# SH2_-_17V_BUCK_CONVERTER.net
KiCad netlist of a schematic drawn in Altium Designer
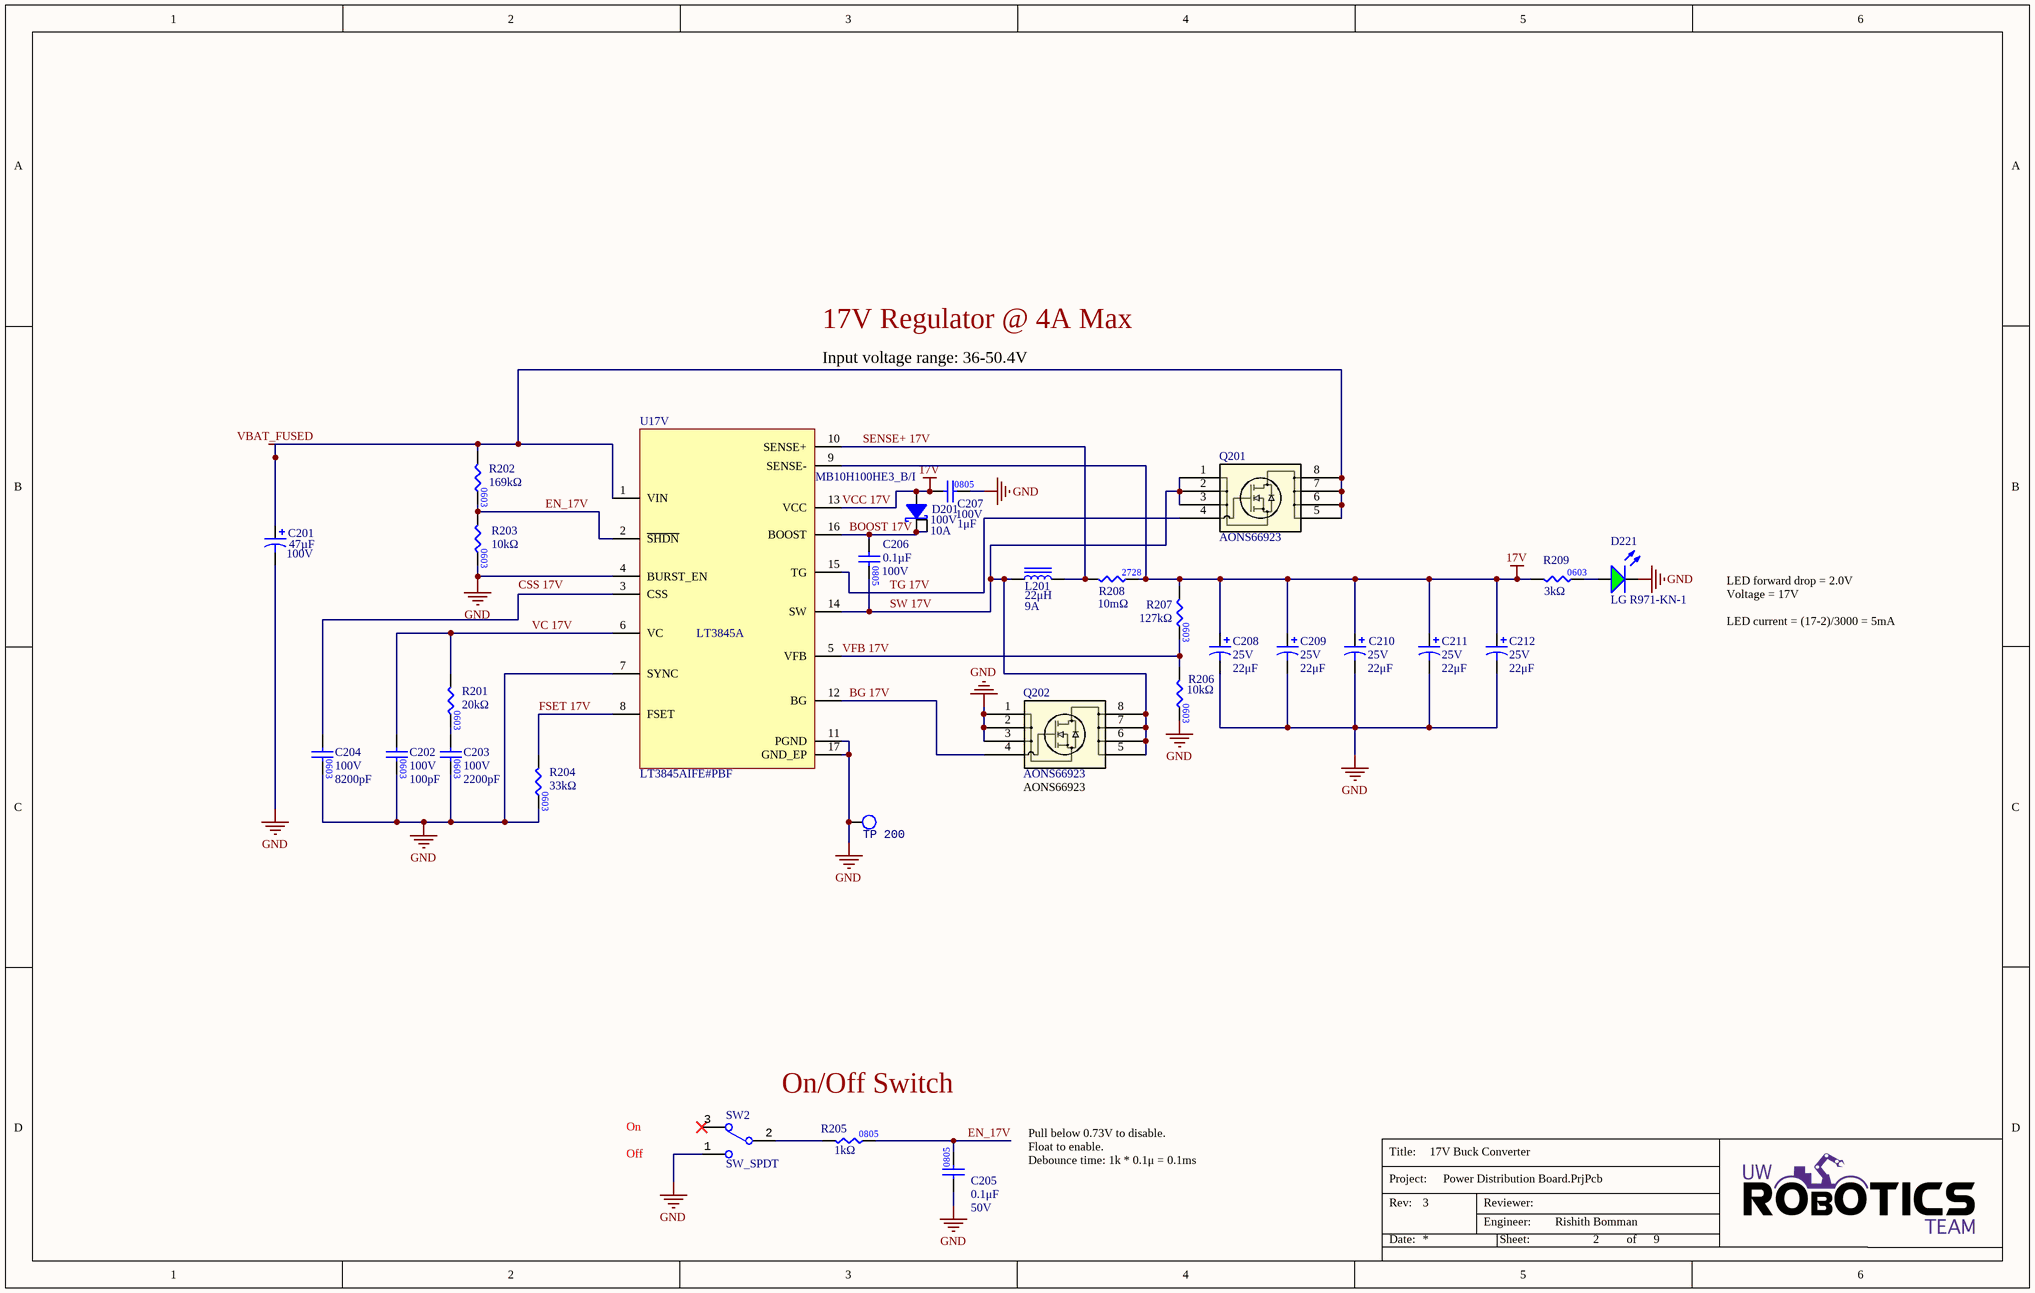
[diagram p0: SH2 - 17V BUCK CONVERTER.SchDoc]

(export (version "E")
  (design (tool "Eeschema 10.0.6"))
  (components
    (comp (ref "C201")
      (value "47µF")
      (footprint "CAP_UCD_10X10_NCH-M")
      (description "CAP ALUM 47UF 20% 100V SMD")
      (fields (field (name "VOLTAGE RATING") "100V") (field (name "Comment") "CAP_47uF_100V_ALUM_1"))
      (libsource (lib "UWRT_Schematic_Library_2020") (part "CAP_47uF_100V_ALUM_1"))
    )
    (comp (ref "C202")
      (value "100pF")
      (footprint "CAP0603")
      (description "CAP CER 100PF 100V C0G/NP0 0603")
      (fields (field (name "VOLTAGE RATING") "100V") (field (name "Comment") "CAP_100pF_100V_0603"))
      (libsource (lib "UWRT_Schematic_Library_2020") (part "CAP_100pF_100V_0603"))
    )
    (comp (ref "C203")
      (value "2200pF")
      (footprint "CAP0603")
      (description "CAP CER 2200PF 100V X7R 0603")
      (fields (field (name "VOLTAGE RATING") "100V") (field (name "Comment") "CAP_2200pF_100V_0603"))
      (libsource (lib "UWRT_Schematic_Library_2020") (part "CAP_2200pF_100V_0603"))
    )
    (comp (ref "C204")
      (value "8200pF")
      (footprint "CAP0603")
      (description "CAP CER 8200PF 100V X7R 0603")
      (fields (field (name "VOLTAGE RATING") "100V") (field (name "Comment") "CAP_8200pF_100V_0603"))
      (libsource (lib "UWRT_Schematic_Library_2020") (part "CAP_8200pF_100V_0603"))
    )
    (comp (ref "C205")
      (value "0.1μF")
      (footprint "CAP2012")
      (description "CAP CER 0.1UF 50V X7R 0805")
      (fields
        (field (name "VOLTAGE RATING") "50V")
        (field (name "LCSC PART #") "C49678")
        (field (name "Comment") "CAP_0.1uF_50V_0805")
      )
      (libsource (lib "UWRT_Schematic_Library_2020") (part "CAP_0.1uF_50V_0805"))
    )
    (comp (ref "C206")
      (value "0.1µF")
      (footprint "CAP0805")
      (description "CAP CER 0.1UF 100V X7R 0805")
      (fields (field (name "VOLTAGE RATING") "100V") (field (name "Comment") "CAP_0.1uF_100V_0805"))
      (libsource (lib "UWRT_Schematic_Library_2020") (part "CAP_0.1uF_100V_0805"))
    )
    (comp (ref "C207")
      (value "1μF")
      (footprint "CAP2012")
      (description "CAP CER 1UF 100V X7S 0805")
      (fields
        (field (name "LCSC PART #") "C5378")
        (field (name "VOLTAGE RATING") "100V")
        (field (name "Comment") "CAP_1uF_100V_0805")
      )
      (libsource (lib "UWRT_Schematic_Library_2020") (part "CAP_1uF_100V_0805"))
    )
    (comp (ref "C208")
      (value "22μF")
      (footprint "CAP2917")
      (description "CAP TANT 22UF 20% 25V 2917")
      (fields (field (name "VOLTAGE RATING") "25V") (field (name "Comment") "CAP_22uF_25V_TANT"))
      (libsource (lib "UWRT_Schematic_Library_2020") (part "CAP_22uF_25V_TANT"))
    )
    (comp (ref "C209")
      (value "22μF")
      (footprint "CAP2917")
      (description "CAP TANT 22UF 20% 25V 2917")
      (fields (field (name "VOLTAGE RATING") "25V") (field (name "Comment") "CAP_22uF_25V_TANT"))
      (libsource (lib "UWRT_Schematic_Library_2020") (part "CAP_22uF_25V_TANT"))
    )
    (comp (ref "C210")
      (value "22μF")
      (footprint "CAP2917")
      (description "CAP TANT 22UF 20% 25V 2917")
      (fields (field (name "VOLTAGE RATING") "25V") (field (name "Comment") "CAP_22uF_25V_TANT"))
      (libsource (lib "UWRT_Schematic_Library_2020") (part "CAP_22uF_25V_TANT"))
    )
    (comp (ref "C211")
      (value "22μF")
      (footprint "CAP2917")
      (description "CAP TANT 22UF 20% 25V 2917")
      (fields (field (name "VOLTAGE RATING") "25V") (field (name "Comment") "CAP_22uF_25V_TANT"))
      (libsource (lib "UWRT_Schematic_Library_2020") (part "CAP_22uF_25V_TANT"))
    )
    (comp (ref "C212")
      (value "22μF")
      (footprint "CAP2917")
      (description "CAP TANT 22UF 20% 25V 2917")
      (fields (field (name "VOLTAGE RATING") "25V") (field (name "Comment") "CAP_22uF_25V_TANT"))
      (libsource (lib "UWRT_Schematic_Library_2020") (part "CAP_22uF_25V_TANT"))
    )
    (comp (ref "D201")
      (value "DIO_SCHOTTKY_100V_5.5A")
      (footprint "D-PAK3")
      (description "DIODE SCHOTTKY 100V 10A TO263AB")
      (fields
        (field (name "FORWARD CURRENT") "10A")
        (field (name "MANUFACTURER PART NUMBER 1") "MB10H100HE3_B/I")
        (field (name "VR (MAX)") "100V")
      )
      (libsource (lib "UWRT_Schematic_Library_2020") (part "DIO_SCHOTTKY_100V_10A"))
    )
    (comp (ref "D221")
      (value "LED_GREEN")
      (footprint "LED_0805_GREEN")
      (description "LED GREEN DIFFUSED 0805 SMD")
      (fields (field (name "MANUFACTURER PART NUMBER 1") "LG R971-KN-1"))
      (libsource (lib "UWRT_Schematic_Library_2020") (part "LED_GREEN"))
    )
    (comp (ref "L201")
      (value "IND_22uH_9A")
      (footprint "IND_BOURNS_SRP1265")
      (description "22UH 20%  SMD POWER CHOKE")
      (fields (field (name "CURRENT RATING") "9A") (field (name "INDUCTANCE") "22μH"))
      (libsource (lib "UWRT_Schematic_Library_2020") (part "IND_22uH_9A"))
    )
    (comp (ref "Q201")
      (value "AONS66923")
      (footprint "DFN5X6_8L_EP1_P_AOS-L")
      (description "MOSFET N-CH 100V 15A/47A 8DFN")
      (fields (field (name "COPYRIGHT") "Copyright (C) 2022 Ultra Librarian. All rights reserved."))
      (libsource (lib "UWRT_Schematic_Library_2020") (part "NMOS_100V_15/47A_1"))
    )
    (comp (ref "Q202")
      (value "AONS66923")
      (footprint "DFN5X6_8L_EP1_P_AOS-L")
      (description "MOSFET N-CH 100V 15A/47A 8DFN")
      (fields
        (field (name "MANUFACTURER_PART_NUMBER") "AONS66923")
        (field (name "COPYRIGHT") "Copyright (C) 2022 Ultra Librarian. All rights reserved.")
      )
      (libsource (lib "UWRT_Schematic_Library_2020") (part "NMOS_100V_15/47A_1"))
    )
    (comp (ref "R201")
      (value "20kΩ")
      (footprint "RES0603")
      (description "RES 20K OHM 1% 1/10W 0603")
      (fields (field (name "Comment") "RES_20kΩ_0603_1%"))
      (libsource (lib "UWRT_Schematic_Library_2020") (part "RES_20kΩ_0603_1%"))
    )
    (comp (ref "R202")
      (value "169kΩ")
      (footprint "RES0603")
      (description "RES 169K OHM 1% 1/10W 0603")
      (fields (field (name "Comment") "RES_169kΩ_0603_1%"))
      (libsource (lib "UWRT_Schematic_Library_2020") (part "RES_169kΩ_0603_1%"))
    )
    (comp (ref "R203")
      (value "10kΩ")
      (footprint "RES0603")
      (description "RES 10K OHM 5% 1/10W 0603")
      (fields (field (name "Comment") "RES_10kΩ_0603_5%"))
      (libsource (lib "UWRT_Schematic_Library_2020") (part "RES_10kΩ_0603_5%"))
    )
    (comp (ref "R204")
      (value "33kΩ")
      (footprint "RES0603")
      (description "RES 33K OHM 5% 1/10W 0603")
      (fields (field (name "Comment") "RES_33kΩ_0603_5%"))
      (libsource (lib "UWRT_Schematic_Library_2020") (part "RES_33kΩ_0603_5%"))
    )
    (comp (ref "R205")
      (value "1kΩ")
      (footprint "RES0805")
      (description "RES 1K OHM 1% 1/8W 0805")
      (fields (field (name "LCSC PART #") "C17513") (field (name "Comment") "RES_1kΩ_0805_1%_1"))
      (libsource (lib "UWRT_Schematic_Library_2020") (part "RES_1kΩ_0805_1%_1"))
    )
    (comp (ref "R206")
      (value "10kΩ")
      (footprint "RES0603")
      (description "RES 10K OHM 5% 1/10W 0603")
      (fields (field (name "Comment") "RES_10kΩ_0603_5%"))
      (libsource (lib "UWRT_Schematic_Library_2020") (part "RES_10kΩ_0603_5%"))
    )
    (comp (ref "R207")
      (value "127kΩ")
      (footprint "RES0603")
      (description "RES 127K OHM 1% 1/10W 0603")
      (fields (field (name "Comment") "RES_127kΩ_0603_1%"))
      (libsource (lib "UWRT_Schematic_Library_2020") (part "RES_127kΩ_0603_1%"))
    )
    (comp (ref "R208")
      (value "10mΩ")
      (footprint "STAC-CSS2725-099H_V")
      (description "RES 10mOHM 1% 4W 2728")
      (fields (field (name "Comment") "RES_10mΩ_2728_1%"))
      (libsource (lib "UWRT_Schematic_Library_2020") (part "RES_10mΩ_2728_1%"))
    )
    (comp (ref "R209")
      (value "3kΩ")
      (footprint "RES0603")
      (description "RES 3K OHM 1% 1/10W 0603")
      (fields (field (name "Comment") "RES_3kΩ_0603_1%"))
      (libsource (lib "UWRT_Schematic_Library_2020") (part "RES_3kΩ_0603_1%"))
    )
    (comp (ref "SW2")
      (value "SW_SPDT")
      (footprint "100SP1T1B4M2QE")
      (description "SWITCH TOGGLE SPDT 5A 120V")
      (libsource (lib "UWRT_Schematic_Library_2020") (part "SW_SPDT"))
    )
    (comp (ref "TP 200")
      (value "TESTPOINT_LOOP")
      (footprint "TESTPOINT_LOOP")
      (description "TESTPOINT THRUHOLE")
      (libsource (lib "UWRT_Schematic_Library_2020") (part "TESTPOINT_LOOP"))
    )
    (comp (ref "U17V")
      (value "BUCK_LT3845A")
      (footprint "LT3845AIFE#PBF")
      (description "IC REG CTRLR BUCK 16TSSOP")
      (fields (field (name "MANUFACTURER PART NUMBER 1") "LT3845AIFE#PBF"))
      (libsource (lib "UWRT_Schematic_Library_2020") (part "BUCK_LT3845A"))
    )
  )
  (nets
    (net (code "1") (name "/BG 17V") (class "Default")
      (node (ref "Q202") (pin "4") (pinfunction "4_4") (pintype "passive"))
      (node (ref "U17V") (pin "12") (pinfunction "BG_12") (pintype "passive"))
    )
    (net (code "2") (name "/BOOST 17V") (class "Default")
      (node (ref "C206") (pin "1") (pinfunction "1_1") (pintype "passive"))
      (node (ref "D201") (pin "1") (pinfunction "Cathode_1") (pintype "passive"))
      (node (ref "D201") (pin "3") (pinfunction "Heatsink_(K)_3") (pintype "passive"))
      (node (ref "U17V") (pin "16") (pinfunction "BOOST_16") (pintype "passive"))
    )
    (net (code "4") (name "/EN_17V") (class "Default")
      (node (ref "C205") (pin "2") (pinfunction "2_2") (pintype "passive"))
      (node (ref "R202") (pin "2") (pinfunction "2_2") (pintype "passive"))
      (node (ref "R203") (pin "1") (pinfunction "1_1") (pintype "passive"))
      (node (ref "R205") (pin "2") (pinfunction "2_2") (pintype "passive"))
      (node (ref "U17V") (pin "2") (pinfunction "~{SHDN}_2") (pintype "passive"))
    )
    (net (code "5") (name "/FSET 17V") (class "Default")
      (node (ref "R204") (pin "1") (pinfunction "1_1") (pintype "passive"))
      (node (ref "U17V") (pin "8") (pinfunction "FSET_8") (pintype "passive"))
    )
    (net (code "6") (name "/SENSE+ 17V") (class "Default")
      (node (ref "L201") (pin "2") (pinfunction "2_2") (pintype "passive"))
      (node (ref "R208") (pin "1") (pinfunction "1_1") (pintype "passive"))
      (node (ref "U17V") (pin "10") (pinfunction "SENSE+_10") (pintype "passive"))
    )
    (net (code "7") (name "/SW 17V") (class "Default")
      (node (ref "C206") (pin "2") (pinfunction "2_2") (pintype "passive"))
      (node (ref "L201") (pin "1") (pinfunction "1_1") (pintype "passive"))
      (node (ref "Q201") (pin "1") (pinfunction "1_1") (pintype "passive"))
      (node (ref "Q201") (pin "2") (pinfunction "2_2") (pintype "passive"))
      (node (ref "Q201") (pin "3") (pinfunction "3_3") (pintype "passive"))
      (node (ref "Q202") (pin "5") (pinfunction "5_5") (pintype "passive"))
      (node (ref "Q202") (pin "6") (pinfunction "6_6") (pintype "passive"))
      (node (ref "Q202") (pin "7") (pinfunction "7_7") (pintype "passive"))
      (node (ref "Q202") (pin "8") (pinfunction "8_8") (pintype "passive"))
      (node (ref "U17V") (pin "14") (pinfunction "SW_14") (pintype "passive"))
    )
    (net (code "8") (name "/TG 17V") (class "Default")
      (node (ref "Q201") (pin "4") (pinfunction "4_4") (pintype "passive"))
      (node (ref "U17V") (pin "15") (pinfunction "TG_15") (pintype "passive"))
    )
    (net (code "9") (name "/VC 17V") (class "Default")
      (node (ref "C202") (pin "1") (pinfunction "1_1") (pintype "passive"))
      (node (ref "R201") (pin "1") (pinfunction "1_1") (pintype "passive"))
      (node (ref "U17V") (pin "6") (pinfunction "VC_6") (pintype "passive"))
    )
    (net (code "10") (name "/VFB 17V") (class "Default")
      (node (ref "R206") (pin "1") (pinfunction "1_1") (pintype "passive"))
      (node (ref "R207") (pin "2") (pinfunction "2_2") (pintype "passive"))
      (node (ref "U17V") (pin "5") (pinfunction "VFB_5") (pintype "passive"))
    )
    (net (code "11") (name "17V") (class "Default")
      (node (ref "C207") (pin "1") (pinfunction "1_1") (pintype "passive"))
      (node (ref "C208") (pin "1") (pinfunction "1_1") (pintype "passive"))
      (node (ref "C209") (pin "1") (pinfunction "1_1") (pintype "passive"))
      (node (ref "C210") (pin "1") (pinfunction "1_1") (pintype "passive"))
      (node (ref "C211") (pin "1") (pinfunction "1_1") (pintype "passive"))
      (node (ref "C212") (pin "1") (pinfunction "1_1") (pintype "passive"))
      (node (ref "D201") (pin "2") (pinfunction "Anode_2") (pintype "passive"))
      (node (ref "R207") (pin "1") (pinfunction "1_1") (pintype "passive"))
      (node (ref "R208") (pin "2") (pinfunction "2_2") (pintype "passive"))
      (node (ref "R209") (pin "1") (pinfunction "1_1") (pintype "passive"))
      (node (ref "U17V") (pin "13") (pinfunction "VCC_13") (pintype "passive"))
      (node (ref "U17V") (pin "9") (pinfunction "SENSE-_9") (pintype "passive"))
    )
    (net (code "12") (name "GND") (class "Default")
      (node (ref "C201") (pin "2") (pinfunction "2_2") (pintype "passive"))
      (node (ref "C202") (pin "2") (pinfunction "2_2") (pintype "passive"))
      (node (ref "C203") (pin "2") (pinfunction "2_2") (pintype "passive"))
      (node (ref "C204") (pin "2") (pinfunction "2_2") (pintype "passive"))
      (node (ref "C205") (pin "1") (pinfunction "1_1") (pintype "passive"))
      (node (ref "C207") (pin "2") (pinfunction "2_2") (pintype "passive"))
      (node (ref "C208") (pin "2") (pinfunction "2_2") (pintype "passive"))
      (node (ref "C209") (pin "2") (pinfunction "2_2") (pintype "passive"))
      (node (ref "C210") (pin "2") (pinfunction "2_2") (pintype "passive"))
      (node (ref "C211") (pin "2") (pinfunction "2_2") (pintype "passive"))
      (node (ref "C212") (pin "2") (pinfunction "2_2") (pintype "passive"))
      (node (ref "D221") (pin "2") (pinfunction "K_2") (pintype "passive"))
      (node (ref "Q202") (pin "1") (pinfunction "1_1") (pintype "passive"))
      (node (ref "Q202") (pin "2") (pinfunction "2_2") (pintype "passive"))
      (node (ref "Q202") (pin "3") (pinfunction "3_3") (pintype "passive"))
      (node (ref "R203") (pin "2") (pinfunction "2_2") (pintype "passive"))
      (node (ref "R204") (pin "2") (pinfunction "2_2") (pintype "passive"))
      (node (ref "R206") (pin "2") (pinfunction "2_2") (pintype "passive"))
      (node (ref "SW2") (pin "1") (pinfunction "1_1") (pintype "passive"))
      (node (ref "TP 200") (pin "1") (pintype "passive"))
      (node (ref "U17V") (pin "11") (pinfunction "PGND_11") (pintype "power_in"))
      (node (ref "U17V") (pin "17") (pinfunction "GND_EP_17") (pintype "power_in"))
      (node (ref "U17V") (pin "4") (pinfunction "BURST_EN_4") (pintype "passive"))
      (node (ref "U17V") (pin "7") (pinfunction "SYNC_7") (pintype "passive"))
    )
    (net (code "13") (name "Net-(C203-Pad1)") (class "Default")
      (node (ref "C203") (pin "1") (pinfunction "1_1") (pintype "passive"))
      (node (ref "R201") (pin "2") (pinfunction "2_2") (pintype "passive"))
    )
    (net (code "14") (name "Net-(D221-A)") (class "Default")
      (node (ref "D221") (pin "1") (pinfunction "A_1") (pintype "passive"))
      (node (ref "R209") (pin "2") (pinfunction "2_2") (pintype "passive"))
    )
    (net (code "15") (name "Net-(R205-Pad1)") (class "Default")
      (node (ref "R205") (pin "1") (pinfunction "1_1") (pintype "passive"))
      (node (ref "SW2") (pin "2") (pinfunction "2_2") (pintype "passive"))
    )
    (net (code "16") (name "Net-(U17V-CSS)") (class "Default")
      (node (ref "C204") (pin "1") (pinfunction "1_1") (pintype "passive"))
      (node (ref "U17V") (pin "3") (pinfunction "CSS_3") (pintype "passive"))
    )
    (net (code "17") (name "VBAT_FUSED") (class "Default")
      (node (ref "C201") (pin "1") (pinfunction "1_1") (pintype "passive"))
      (node (ref "Q201") (pin "5") (pinfunction "5_5") (pintype "passive"))
      (node (ref "Q201") (pin "6") (pinfunction "6_6") (pintype "passive"))
      (node (ref "Q201") (pin "7") (pinfunction "7_7") (pintype "passive"))
      (node (ref "Q201") (pin "8") (pinfunction "8_8") (pintype "passive"))
      (node (ref "R202") (pin "1") (pinfunction "1_1") (pintype "passive"))
      (node (ref "U17V") (pin "1") (pinfunction "VIN_1") (pintype "passive"))
    )
    (net (code "18") (name "unconnected-(SW2-Pad3)") (class "Default")
      (node (ref "SW2") (pin "3") (pinfunction "3_3") (pintype "passive+no_connect"))
    )
  )
)
